# Power.net
KiCad netlist of a schematic drawn in Altium Designer
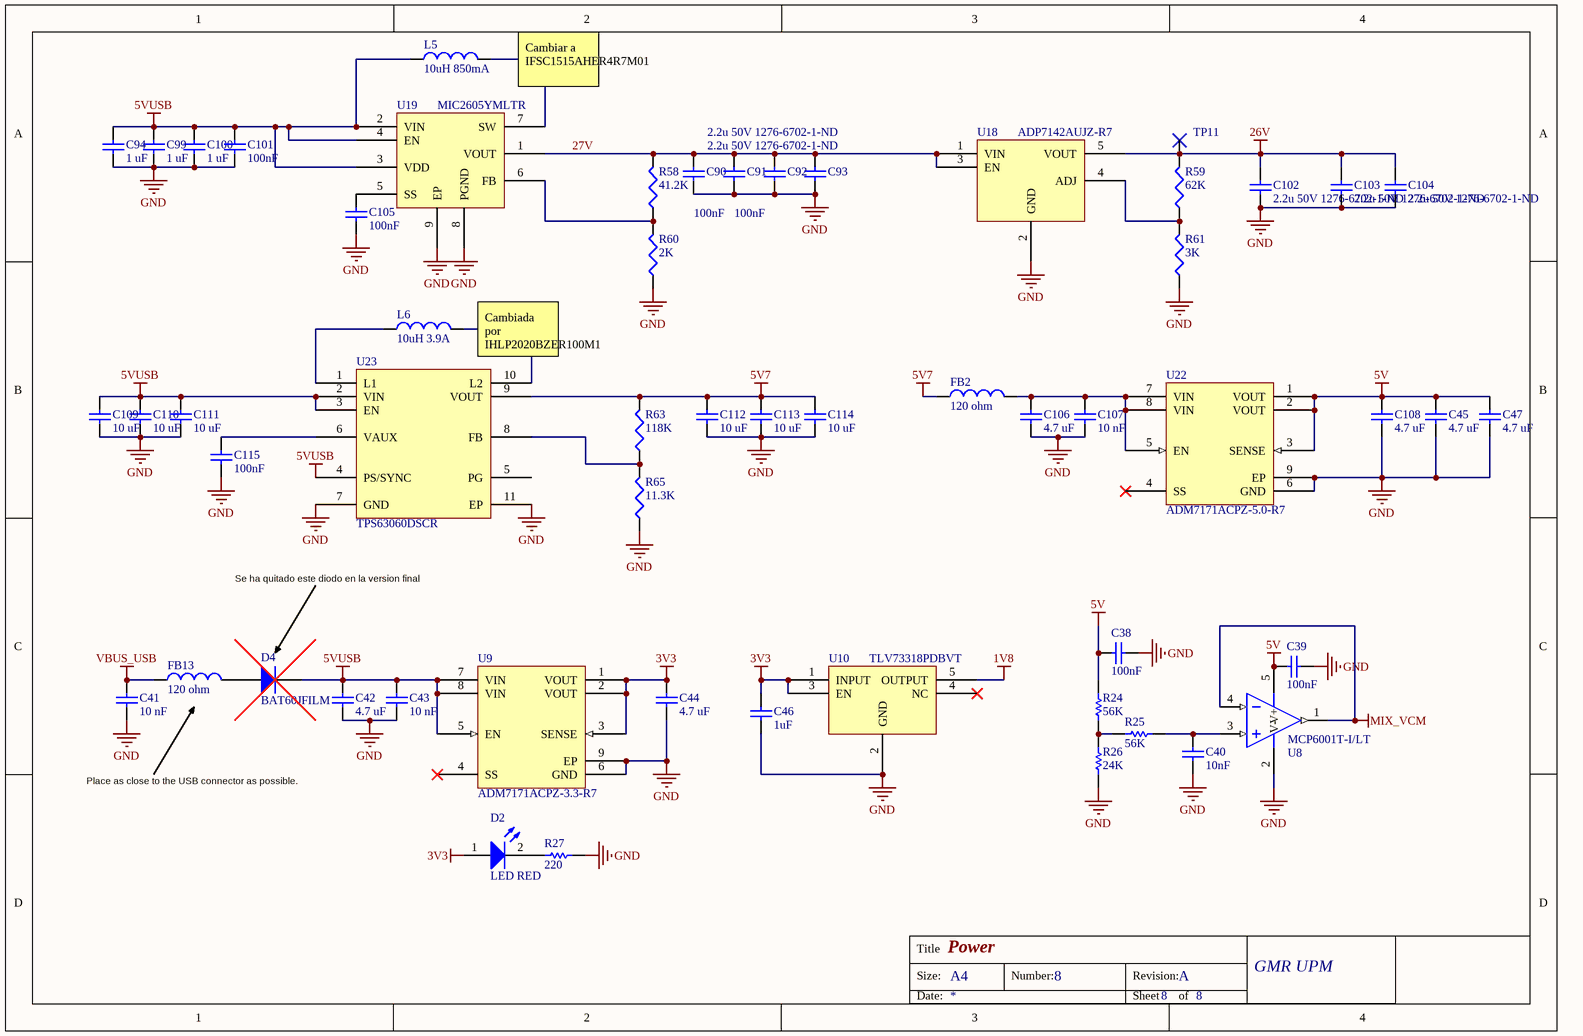
[diagram p0: Power.SchDoc]

(export (version "E")
  (design (tool "Eeschema 10.0.6"))
  (components
    (comp (ref "C38")
      (value "100nF")
      (footprint "0603 Cap")
      (description "CAP CER 16V X7R 0603")
      (fields (field (name "TOLERANCE") "10") (field (name "VOLTAGE") "16"))
      (libsource (lib "Componentes_base") (part "C_0603"))
    )
    (comp (ref "C39")
      (value "100nF")
      (footprint "0603 Cap")
      (description "CAP CER 16V X7R 0603")
      (fields (field (name "TOLERANCE") "10") (field (name "VOLTAGE") "16"))
      (libsource (lib "Componentes_base") (part "C_0603"))
    )
    (comp (ref "C40")
      (value "10nF")
      (footprint "0603 Cap")
      (description "CAP CER 16V X7R 0603")
      (fields (field (name "TOLERANCE") "10") (field (name "VOLTAGE") "16"))
      (libsource (lib "Componentes_base") (part "C_0603"))
    )
    (comp (ref "C41")
      (value "10 nF")
      (footprint "Chip2PinSM127P600-8N_CAP0402")
      (description "CAP CER 10000PF 25V X7R 0402")
      (fields
        (field (name "MANUFACTURER") "Samsung Electro-Mechanics America, Inc.")
        (field (name "MANUFACTURER PART NUMBER") "CL05B103KA5NNNC")
      )
      (libsource (lib "Components") (part "CL05B103KA5NNNC"))
    )
    (comp (ref "C42")
      (value "4.7 uF")
      (footprint "CAPC1608X10L")
      (description "Multilayer Ceramic Capacitors MLCC - SMD/SMT 0603 4.7uF 16volts X5R + - 10%")
      (fields
        (field (name "MANUFACTURER") "Murata Electronics")
        (field (name "MANUFACTURER PART NUMBER") "GRM188R61C475KAAJD")
      )
      (libsource (lib "Components") (part "GRM188R61C475KAAJD"))
    )
    (comp (ref "C43")
      (value "10 nF")
      (footprint "Chip2PinSM127P600-8N_CAP0402")
      (description "CAP CER 10000PF 25V X7R 0402")
      (fields
        (field (name "MANUFACTURER") "Samsung Electro-Mechanics America, Inc.")
        (field (name "MANUFACTURER PART NUMBER") "CL05B103KA5NNNC")
      )
      (libsource (lib "Components") (part "CL05B103KA5NNNC"))
    )
    (comp (ref "C44")
      (value "4.7 uF")
      (footprint "CAPC1608X10L")
      (description "Multilayer Ceramic Capacitors MLCC - SMD/SMT 0603 4.7uF 16volts X5R + - 10%")
      (fields
        (field (name "MANUFACTURER") "Murata Electronics")
        (field (name "MANUFACTURER PART NUMBER") "GRM188R61C475KAAJD")
      )
      (libsource (lib "Components") (part "GRM188R61C475KAAJD"))
    )
    (comp (ref "C45")
      (value "4.7 uF")
      (footprint "CAPC1608X10L")
      (description "Multilayer Ceramic Capacitors MLCC - SMD/SMT 0603 4.7uF 16volts X5R + - 10%")
      (fields
        (field (name "MANUFACTURER") "Murata Electronics")
        (field (name "MANUFACTURER PART NUMBER") "GRM188R61C475KAAJD")
      )
      (libsource (lib "Components") (part "GRM188R61C475KAAJD"))
    )
    (comp (ref "C46")
      (value "1uF")
      (footprint "0603 Cap")
      (description "CAP CER 1UF 16V X7R 0603")
      (fields
        (field (name "MANUFACTURER") "Samsung Electro-Mechanics America, Inc.")
        (field (name "MANUFACTURER PART NUMBER") "CL10B105MO8NNWC")
      )
      (libsource (lib "Componentes_base") (part "CL10B105MO8NNWC"))
    )
    (comp (ref "C47")
      (value "4.7 uF")
      (footprint "CAPC1608X10L")
      (description "Multilayer Ceramic Capacitors MLCC - SMD/SMT 0603 4.7uF 16volts X5R + - 10%")
      (fields
        (field (name "MANUFACTURER") "Murata Electronics")
        (field (name "MANUFACTURER PART NUMBER") "GRM188R61C475KAAJD")
      )
      (libsource (lib "Components") (part "GRM188R61C475KAAJD"))
    )
    (comp (ref "C90")
      (value "100nF")
      (footprint "0603 Cap")
      (description "CAP CER 0.1UF 16V X7R 0603")
      (fields
        (field (name "MANUFACTURER") "KEMET")
        (field (name "MANUFACTURER PART NUMBER") "C0603C104K4RACTU")
      )
      (libsource (lib "Componentes_base") (part "C0603C104K4RACTU"))
    )
    (comp (ref "C91")
      (value "100nF")
      (footprint "0603 Cap")
      (description "CAP CER 0.1UF 16V X7R 0603")
      (fields
        (field (name "MANUFACTURER") "KEMET")
        (field (name "MANUFACTURER PART NUMBER") "C0603C104K4RACTU")
      )
      (libsource (lib "Componentes_base") (part "C0603C104K4RACTU"))
    )
    (comp (ref "C92")
      (value "2.2u 50V 1276-6702-1-ND")
      (footprint "0805 CAP")
      (description "Multilayer Ceramic Capacitors MLCC - SMD/SMT 16volts 3.3uF X5R 10%")
      (fields
        (field (name "MANUFACTURER") "Kemet")
        (field (name "MANUFACTURER PART NUMBER") "C0805C335K4PACTU")
      )
      (libsource (lib "Componentes_base") (part "C0805C335K4PACTU"))
    )
    (comp (ref "C93")
      (value "2.2u 50V 1276-6702-1-ND")
      (footprint "0805 CAP")
      (description "Multilayer Ceramic Capacitors MLCC - SMD/SMT 16volts 3.3uF X5R 10%")
      (fields
        (field (name "MANUFACTURER") "Kemet")
        (field (name "MANUFACTURER PART NUMBER") "C0805C335K4PACTU")
      )
      (libsource (lib "Componentes_base") (part "C0805C335K4PACTU"))
    )
    (comp (ref "C94")
      (value "1 uF")
      (footprint "CAPC2012X08L")
      (description "CAP CER 1UF 25V 10% X7R 0805")
      (fields
        (field (name "MANUFACTURER") "Samsung Electro-Mechanics America, Inc")
        (field (name "MANUFACTURER PART NUMBER") "CL21B105KAFNNNE")
      )
      (libsource (lib "Componentes_base") (part "CL21B105KAFNNNE"))
    )
    (comp (ref "C99")
      (value "1 uF")
      (footprint "CAPC2012X08L")
      (description "CAP CER 1UF 25V 10% X7R 0805")
      (fields
        (field (name "MANUFACTURER") "Samsung Electro-Mechanics America, Inc")
        (field (name "MANUFACTURER PART NUMBER") "CL21B105KAFNNNE")
      )
      (libsource (lib "Componentes_base") (part "CL21B105KAFNNNE"))
    )
    (comp (ref "C100")
      (value "1 uF")
      (footprint "CAPC2012X08L")
      (description "CAP CER 1UF 25V 10% X7R 0805")
      (fields
        (field (name "MANUFACTURER") "Samsung Electro-Mechanics America, Inc")
        (field (name "MANUFACTURER PART NUMBER") "CL21B105KAFNNNE")
      )
      (libsource (lib "Componentes_base") (part "CL21B105KAFNNNE"))
    )
    (comp (ref "C101")
      (value "100nF")
      (footprint "0603 Cap")
      (description "CAP CER 0.1UF 16V X7R 0603")
      (fields
        (field (name "MANUFACTURER") "KEMET")
        (field (name "MANUFACTURER PART NUMBER") "C0603C104K4RACTU")
      )
      (libsource (lib "Componentes_base") (part "C0603C104K4RACTU"))
    )
    (comp (ref "C102")
      (value "2.2u 50V 1276-6702-1-ND")
      (footprint "0805 CAP")
      (description "Multilayer Ceramic Capacitors MLCC - SMD/SMT 16volts 3.3uF X5R 10%")
      (fields
        (field (name "MANUFACTURER") "Kemet")
        (field (name "MANUFACTURER PART NUMBER") "C0805C335K4PACTU")
      )
      (libsource (lib "Componentes_base") (part "C0805C335K4PACTU"))
    )
    (comp (ref "C103")
      (value "2.2u 50V 1276-6702-1-ND")
      (footprint "0805 CAP")
      (description "Multilayer Ceramic Capacitors MLCC - SMD/SMT 16volts 3.3uF X5R 10%")
      (fields
        (field (name "MANUFACTURER") "Kemet")
        (field (name "MANUFACTURER PART NUMBER") "C0805C335K4PACTU")
      )
      (libsource (lib "Componentes_base") (part "C0805C335K4PACTU"))
    )
    (comp (ref "C104")
      (value "2.2u 50V 1276-6702-1-ND")
      (footprint "0805 CAP")
      (description "Multilayer Ceramic Capacitors MLCC - SMD/SMT 16volts 3.3uF X5R 10%")
      (fields
        (field (name "MANUFACTURER") "Kemet")
        (field (name "MANUFACTURER PART NUMBER") "C0805C335K4PACTU")
      )
      (libsource (lib "Componentes_base") (part "C0805C335K4PACTU"))
    )
    (comp (ref "C105")
      (value "100nF")
      (footprint "0603 Cap")
      (description "CAP CER 0.1UF 16V X7R 0603")
      (fields
        (field (name "MANUFACTURER") "KEMET")
        (field (name "MANUFACTURER PART NUMBER") "C0603C104K4RACTU")
      )
      (libsource (lib "Componentes_base") (part "C0603C104K4RACTU"))
    )
    (comp (ref "C106")
      (value "4.7 uF")
      (footprint "CAPC1608X10L")
      (description "Multilayer Ceramic Capacitors MLCC - SMD/SMT 0603 4.7uF 16volts X5R + - 10%")
      (fields
        (field (name "MANUFACTURER") "Murata Electronics")
        (field (name "MANUFACTURER PART NUMBER") "GRM188R61C475KAAJD")
      )
      (libsource (lib "Components") (part "GRM188R61C475KAAJD"))
    )
    (comp (ref "C107")
      (value "10 nF")
      (footprint "Chip2PinSM127P600-8N_CAP0402")
      (description "CAP CER 10000PF 25V X7R 0402")
      (fields
        (field (name "MANUFACTURER") "Samsung Electro-Mechanics America, Inc.")
        (field (name "MANUFACTURER PART NUMBER") "CL05B103KA5NNNC")
      )
      (libsource (lib "Components") (part "CL05B103KA5NNNC"))
    )
    (comp (ref "C108")
      (value "4.7 uF")
      (footprint "CAPC1608X10L")
      (description "Multilayer Ceramic Capacitors MLCC - SMD/SMT 0603 4.7uF 16volts X5R + - 10%")
      (fields
        (field (name "MANUFACTURER") "Murata Electronics")
        (field (name "MANUFACTURER PART NUMBER") "GRM188R61C475KAAJD")
      )
      (libsource (lib "Components") (part "GRM188R61C475KAAJD"))
    )
    (comp (ref "C109")
      (value "10 uF")
      (footprint "CAPC2012X08L")
      (description "CAP CER 10UF 25V 10% X5R 0805")
      (fields
        (field (name "MANUFACTURER") "Samsung Electro-Mechanics America, Inc")
        (field (name "MANUFACTURER PART NUMBER") "CL21A106KAYNNNE")
      )
      (libsource (lib "Componentes_base") (part "CL21A106KAYNNNE"))
    )
    (comp (ref "C110")
      (value "10 uF")
      (footprint "CAPC2012X08L")
      (description "CAP CER 10UF 25V 10% X5R 0805")
      (fields
        (field (name "MANUFACTURER") "Samsung Electro-Mechanics America, Inc")
        (field (name "MANUFACTURER PART NUMBER") "CL21A106KAYNNNE")
      )
      (libsource (lib "Componentes_base") (part "CL21A106KAYNNNE"))
    )
    (comp (ref "C111")
      (value "10 uF")
      (footprint "CAPC2012X08L")
      (description "CAP CER 10UF 25V 10% X5R 0805")
      (fields
        (field (name "MANUFACTURER") "Samsung Electro-Mechanics America, Inc")
        (field (name "MANUFACTURER PART NUMBER") "CL21A106KAYNNNE")
      )
      (libsource (lib "Componentes_base") (part "CL21A106KAYNNNE"))
    )
    (comp (ref "C112")
      (value "10 uF")
      (footprint "CAPC2012X08L")
      (description "CAP CER 10UF 25V 10% X5R 0805")
      (fields
        (field (name "MANUFACTURER") "Samsung Electro-Mechanics America, Inc")
        (field (name "MANUFACTURER PART NUMBER") "CL21A106KAYNNNE")
      )
      (libsource (lib "Componentes_base") (part "CL21A106KAYNNNE"))
    )
    (comp (ref "C113")
      (value "10 uF")
      (footprint "CAPC2012X08L")
      (description "CAP CER 10UF 25V 10% X5R 0805")
      (fields
        (field (name "MANUFACTURER") "Samsung Electro-Mechanics America, Inc")
        (field (name "MANUFACTURER PART NUMBER") "CL21A106KAYNNNE")
      )
      (libsource (lib "Componentes_base") (part "CL21A106KAYNNNE"))
    )
    (comp (ref "C114")
      (value "10 uF")
      (footprint "CAPC2012X08L")
      (description "CAP CER 10UF 25V 10% X5R 0805")
      (fields
        (field (name "MANUFACTURER") "Samsung Electro-Mechanics America, Inc")
        (field (name "MANUFACTURER PART NUMBER") "CL21A106KAYNNNE")
      )
      (libsource (lib "Componentes_base") (part "CL21A106KAYNNNE"))
    )
    (comp (ref "C115")
      (value "100nF")
      (footprint "0603 Cap")
      (description "CAP CER 0.1UF 16V X7R 0603")
      (fields
        (field (name "MANUFACTURER") "KEMET")
        (field (name "MANUFACTURER PART NUMBER") "C0603C104K4RACTU")
      )
      (libsource (lib "Componentes_base") (part "C0603C104K4RACTU"))
    )
    (comp (ref "D2")
      (value "LED RED")
      (footprint "0603 LED")
      (description "LED RED CLEAR 0603 SMD")
      (fields
        (field (name "MANUFACTURER") "Lite-On Inc.")
        (field (name "MANUFACTURER PART NUMBER") "LTST-C191KRKT")
      )
      (libsource (lib "Componentes_base") (part "LTST-C191KRKT"))
    )
    (comp (ref "D4")
      (value "BAT60JFILM")
      (footprint "SODFL250X117-2N")
      (description "DIODE SCHOTTKY 10V 3A SOD323")
      (fields (field (name "MANUFACTURER") "STMicroelectronics"))
      (libsource (lib "Componentes_base") (part "BAT60JFILM"))
    )
    (comp (ref "FB2")
      (value "120 ohm")
      (footprint "INDC1608X08L")
      (description "FERRITE BEAD 120 OHM 0603 1LN")
      (fields
        (field (name "MANUFACTURER") "Murata Electronics North America")
        (field (name "MANUFACTURER PART NUMBER") "BLM18PG121SN1D")
      )
      (libsource (lib "Componentes_base") (part "BLM18PG121SN1D"))
    )
    (comp (ref "FB13")
      (value "120 ohm")
      (footprint "INDC1608X08L")
      (description "FERRITE BEAD 120 OHM 0603 1LN")
      (fields
        (field (name "MANUFACTURER") "Murata Electronics North America")
        (field (name "MANUFACTURER PART NUMBER") "BLM18PG121SN1D")
      )
      (libsource (lib "Componentes_base") (part "BLM18PG121SN1D"))
    )
    (comp (ref "L5")
      (value "10uH 850mA")
      (footprint "INDP4040X20N")
      (description "FIXED IND 10UH 850MA 185 MOHM")
      (fields
        (field (name "MANUFACTURER") "TDK")
        (field (name "MANUFACTURER PART NUMBER") "VLCF4020T-100MR85")
      )
      (libsource (lib "Schlib1") (part "VLCF4020T-100MR85"))
    )
    (comp (ref "L6")
      (value "10uH 3.9A")
      (footprint "INDP8080X45N")
      (description "Ind Power Shielded 10uH 20% 100KHz Ferrite 3.9A T/R")
      (fields
        (field (name "MANUFACTURER") "Murata")
        (field (name "MANUFACTURER PART NUMBER") "1217AS-H-100M=P3")
      )
      (libsource (lib "Schlib1") (part "1217AS-H-100M=P3"))
    )
    (comp (ref "R24")
      (value "56K")
      (footprint "0603 Res")
      (description "SMD Resistor, 1%, 0.1W, 0603")
      (fields (field (name "TOLERANCE") "1"))
      (libsource (lib "Componentes_base") (part "R_0603"))
    )
    (comp (ref "R25")
      (value "56K")
      (footprint "0603 Res")
      (description "SMD Resistor, 1%, 0.1W, 0603")
      (fields (field (name "TOLERANCE") "1"))
      (libsource (lib "Componentes_base") (part "R_0603"))
    )
    (comp (ref "R26")
      (value "24K")
      (footprint "0603 Res")
      (description "SMD Resistor, 1%, 0.1W, 0603")
      (fields (field (name "TOLERANCE") "1"))
      (libsource (lib "Componentes_base") (part "R_0603"))
    )
    (comp (ref "R27")
      (value "220")
      (footprint "0603 Res")
      (description "RES SMD 220 OHM 1% 1/10W 0603")
      (fields
        (field (name "MANUFACTURER") "Yageo")
        (field (name "MANUFACTURER PART NUMBER") "RC0603FR-07220RL")
      )
      (libsource (lib "Componentes_base") (part "RC0603FR-07220RL"))
    )
    (comp (ref "R58")
      (value "41.2K")
      (footprint "J1-0603")
      (description "Resistor")
      (fields (field (name "PUBLISHER") "Altium Limited"))
      (libsource (lib "Miscellaneous Devices") (part "Res3"))
    )
    (comp (ref "R59")
      (value "62K")
      (footprint "J1-0603")
      (description "Resistor")
      (fields (field (name "PUBLISHER") "Altium Limited"))
      (libsource (lib "Miscellaneous Devices") (part "Res3"))
    )
    (comp (ref "R60")
      (value "2K")
      (footprint "J1-0603")
      (description "Resistor")
      (fields (field (name "PUBLISHER") "Altium Limited"))
      (libsource (lib "Miscellaneous Devices") (part "Res3"))
    )
    (comp (ref "R61")
      (value "3K")
      (footprint "J1-0603")
      (description "Resistor")
      (fields (field (name "PUBLISHER") "Altium Limited"))
      (libsource (lib "Miscellaneous Devices") (part "Res3"))
    )
    (comp (ref "R63")
      (value "118K")
      (footprint "J1-0603")
      (description "Resistor")
      (fields (field (name "PUBLISHER") "Altium Limited"))
      (libsource (lib "Miscellaneous Devices") (part "Res3"))
    )
    (comp (ref "R65")
      (value "11.3K")
      (footprint "J1-0603")
      (description "Resistor")
      (fields (field (name "PUBLISHER") "Altium Limited"))
      (libsource (lib "Miscellaneous Devices") (part "Res3"))
    )
    (comp (ref "TP11")
      (value "TEST_POINT_PIN")
      (footprint "TESTPOINT 1mm")
      (description "Test point for single pin")
      (libsource (lib "Componentes_base") (part "TEST_POINT_PIN"))
    )
    (comp (ref "U8")
      (value "MCP6001T-I/LT")
      (footprint "SC70P210X110-5L")
      (description "Operational Amplifiers - Op Amps Single 1.8V 1MHz")
      (fields (field (name "MANUFACTURER") "Microchip Technology"))
      (libsource (lib "Componentes_base") (part "MCP6001T-I/LT"))
    )
    (comp (ref "U9")
      (value "ADM7171ACPZ-3.3-R7")
      (footprint "SON50P300X80_HS-9N LFCSP_WD Analog")
      (description "IC REG LDO 3.3V 1A 8-LFCSP")
      (fields (field (name "MANUFACTURER") "Analog Devices Inc."))
      (libsource (lib "Components") (part "ADM7171ACPZ-3.3-R7"))
    )
    (comp (ref "U10")
      (value "TLV73318PDBVT")
      (footprint "SOT95P280X110-5N")
      (fields (field (name "MANUFACTURER") "Texas Instruments"))
      (libsource (lib "Componentes_base") (part "TLV73318PDBVT"))
    )
    (comp (ref "U18")
      (value "ADP7142AUJZ-R7")
      (footprint "SOT95P280X90-5N")
      (description "LDO Voltage Regulators 40V 200mA LDO adjVo")
      (fields (field (name "MANUFACTURER") "Analog Devices"))
      (libsource (lib "Schlib1") (part "ADP7142AUJZ-R7"))
    )
    (comp (ref "U19")
      (value "MIC2605YMLTR")
      (footprint "SON50P200X90_HS-9N")
      (fields (field (name "MANUFACTURER") "Microchip Micrel"))
      (libsource (lib "Schlib1") (part "MIC2605YMLTR"))
    )
    (comp (ref "U22")
      (value "ADM7171ACPZ-5.0-R7")
      (footprint "SON50P300X80_HS-9N LFCSP_WD Analog")
      (description "LDO Regulator Pos 5V 1A 8-Pin LFCSP T/R")
      (fields (field (name "MANUFACTURER") "Analog Devices"))
      (libsource (lib "Schlib1") (part "ADM7171ACPZ-5.0-R7"))
    )
    (comp (ref "U23")
      (value "TPS63060DSCR")
      (footprint "SON50P300X80_HS-11N")
      (description "IC REG BUCK BOOST ADJ 2A 10WSON")
      (fields (field (name "MANUFACTURER") "Texas Instruments"))
      (libsource (lib "Schlib1") (part "TPS63060DSCR"))
    )
  )
  (nets
    (net (code "1") (name "/27V") (class "Default")
      (node (ref "C90") (pin "2") (pinfunction "2_2") (pintype "passive"))
      (node (ref "C91") (pin "2") (pinfunction "2_2") (pintype "passive"))
      (node (ref "C92") (pin "2") (pinfunction "2_2") (pintype "passive"))
      (node (ref "C93") (pin "2") (pinfunction "2_2") (pintype "passive"))
      (node (ref "R58") (pin "2") (pinfunction "2_2") (pintype "passive"))
      (node (ref "U18") (pin "1") (pinfunction "VIN_1") (pintype "passive"))
      (node (ref "U18") (pin "3") (pinfunction "EN_3") (pintype "passive"))
      (node (ref "U19") (pin "1") (pinfunction "VOUT_1") (pintype "passive"))
    )
    (net (code "2") (name "1V8") (class "Default")
      (node (ref "U10") (pin "5") (pinfunction "OUTPUT_5") (pintype "passive"))
    )
    (net (code "3") (name "3V3") (class "Default")
      (node (ref "C44") (pin "2") (pinfunction "2_2") (pintype "passive"))
      (node (ref "C46") (pin "2") (pinfunction "2_2") (pintype "passive"))
      (node (ref "D2") (pin "1") (pinfunction "A_1") (pintype "passive"))
      (node (ref "U10") (pin "1") (pinfunction "INPUT_1") (pintype "passive"))
      (node (ref "U10") (pin "3") (pinfunction "EN_3") (pintype "passive"))
      (node (ref "U9") (pin "1") (pinfunction "VOUT_1") (pintype "power_in"))
      (node (ref "U9") (pin "2") (pinfunction "VOUT_2") (pintype "power_in"))
      (node (ref "U9") (pin "3") (pinfunction "SENSE_3") (pintype "input"))
    )
    (net (code "4") (name "5V") (class "Default")
      (node (ref "C108") (pin "2") (pinfunction "2_2") (pintype "passive"))
      (node (ref "C38") (pin "1") (pinfunction "1_1") (pintype "passive"))
      (node (ref "C39") (pin "1") (pinfunction "1_1") (pintype "passive"))
      (node (ref "C45") (pin "2") (pinfunction "2_2") (pintype "passive"))
      (node (ref "C47") (pin "2") (pinfunction "2_2") (pintype "passive"))
      (node (ref "R24") (pin "2") (pinfunction "2_2") (pintype "passive"))
      (node (ref "U22") (pin "1") (pinfunction "VOUT_1") (pintype "power_in"))
      (node (ref "U22") (pin "2") (pinfunction "VOUT_2") (pintype "power_in"))
      (node (ref "U22") (pin "3") (pinfunction "SENSE_3") (pintype "input"))
      (node (ref "U8") (pin "5") (pinfunction "V+_5") (pintype "power_in"))
    )
    (net (code "5") (name "5V7") (class "Default")
      (node (ref "C112") (pin "2") (pinfunction "2_2") (pintype "passive"))
      (node (ref "C113") (pin "2") (pinfunction "2_2") (pintype "passive"))
      (node (ref "C114") (pin "2") (pinfunction "2_2") (pintype "passive"))
      (node (ref "FB2") (pin "1") (pinfunction "1_1") (pintype "passive"))
      (node (ref "R63") (pin "2") (pinfunction "2_2") (pintype "passive"))
      (node (ref "U23") (pin "9") (pinfunction "VOUT_9") (pintype "passive"))
    )
    (net (code "6") (name "5VUSB") (class "Default")
      (node (ref "C100") (pin "2") (pinfunction "2_2") (pintype "passive"))
      (node (ref "C101") (pin "2") (pinfunction "2_2") (pintype "passive"))
      (node (ref "C109") (pin "1") (pinfunction "1_1") (pintype "passive"))
      (node (ref "C110") (pin "2") (pinfunction "2_2") (pintype "passive"))
      (node (ref "C111") (pin "2") (pinfunction "2_2") (pintype "passive"))
      (node (ref "C42") (pin "2") (pinfunction "2_2") (pintype "passive"))
      (node (ref "C43") (pin "2") (pinfunction "2_2") (pintype "passive"))
      (node (ref "C94") (pin "2") (pinfunction "2_2") (pintype "passive"))
      (node (ref "C99") (pin "2") (pinfunction "2_2") (pintype "passive"))
      (node (ref "D4") (pin "1") (pinfunction "K_1") (pintype "passive"))
      (node (ref "L5") (pin "1") (pinfunction "1_1") (pintype "passive"))
      (node (ref "U19") (pin "2") (pinfunction "VIN_2") (pintype "passive"))
      (node (ref "U19") (pin "3") (pinfunction "VDD_3") (pintype "passive"))
      (node (ref "U19") (pin "4") (pinfunction "EN_4") (pintype "passive"))
      (node (ref "U23") (pin "2") (pinfunction "VIN_2") (pintype "passive"))
      (node (ref "U23") (pin "3") (pinfunction "EN_3") (pintype "passive"))
      (node (ref "U23") (pin "4") (pinfunction "PS/SYNC_4") (pintype "passive"))
      (node (ref "U9") (pin "5") (pinfunction "EN_5") (pintype "input"))
      (node (ref "U9") (pin "7") (pinfunction "VIN_7") (pintype "power_in"))
      (node (ref "U9") (pin "8") (pinfunction "VIN_8") (pintype "power_in"))
    )
    (net (code "7") (name "26V") (class "Default")
      (node (ref "C102") (pin "2") (pinfunction "2_2") (pintype "passive"))
      (node (ref "C103") (pin "2") (pinfunction "2_2") (pintype "passive"))
      (node (ref "C104") (pin "2") (pinfunction "2_2") (pintype "passive"))
      (node (ref "R59") (pin "2") (pinfunction "2_2") (pintype "passive"))
      (node (ref "TP11") (pin "1") (pinfunction "1_1") (pintype "passive"))
      (node (ref "U18") (pin "5") (pinfunction "VOUT_5") (pintype "passive"))
    )
    (net (code "8") (name "GND") (class "Default")
      (node (ref "C100") (pin "1") (pinfunction "1_1") (pintype "passive"))
      (node (ref "C101") (pin "1") (pinfunction "1_1") (pintype "passive"))
      (node (ref "C102") (pin "1") (pinfunction "1_1") (pintype "passive"))
      (node (ref "C103") (pin "1") (pinfunction "1_1") (pintype "passive"))
      (node (ref "C104") (pin "1") (pinfunction "1_1") (pintype "passive"))
      (node (ref "C105") (pin "1") (pinfunction "1_1") (pintype "passive"))
      (node (ref "C106") (pin "1") (pinfunction "1_1") (pintype "passive"))
      (node (ref "C107") (pin "1") (pinfunction "1_1") (pintype "passive"))
      (node (ref "C108") (pin "1") (pinfunction "1_1") (pintype "passive"))
      (node (ref "C109") (pin "2") (pinfunction "2_2") (pintype "passive"))
      (node (ref "C110") (pin "1") (pinfunction "1_1") (pintype "passive"))
      (node (ref "C111") (pin "1") (pinfunction "1_1") (pintype "passive"))
      (node (ref "C112") (pin "1") (pinfunction "1_1") (pintype "passive"))
      (node (ref "C113") (pin "1") (pinfunction "1_1") (pintype "passive"))
      (node (ref "C114") (pin "1") (pinfunction "1_1") (pintype "passive"))
      (node (ref "C115") (pin "1") (pinfunction "1_1") (pintype "passive"))
      (node (ref "C38") (pin "2") (pinfunction "2_2") (pintype "passive"))
      (node (ref "C39") (pin "2") (pinfunction "2_2") (pintype "passive"))
      (node (ref "C40") (pin "1") (pinfunction "1_1") (pintype "passive"))
      (node (ref "C41") (pin "1") (pinfunction "1_1") (pintype "passive"))
      (node (ref "C42") (pin "1") (pinfunction "1_1") (pintype "passive"))
      (node (ref "C43") (pin "1") (pinfunction "1_1") (pintype "passive"))
      (node (ref "C44") (pin "1") (pinfunction "1_1") (pintype "passive"))
      (node (ref "C45") (pin "1") (pinfunction "1_1") (pintype "passive"))
      (node (ref "C46") (pin "1") (pinfunction "1_1") (pintype "passive"))
      (node (ref "C47") (pin "1") (pinfunction "1_1") (pintype "passive"))
      (node (ref "C90") (pin "1") (pinfunction "1_1") (pintype "passive"))
      (node (ref "C91") (pin "1") (pinfunction "1_1") (pintype "passive"))
      (node (ref "C92") (pin "1") (pinfunction "1_1") (pintype "passive"))
      (node (ref "C93") (pin "1") (pinfunction "1_1") (pintype "passive"))
      (node (ref "C94") (pin "1") (pinfunction "1_1") (pintype "passive"))
      (node (ref "C99") (pin "1") (pinfunction "1_1") (pintype "passive"))
      (node (ref "R26") (pin "1") (pinfunction "1_1") (pintype "passive"))
      (node (ref "R27") (pin "2") (pinfunction "2_2") (pintype "passive"))
      (node (ref "R60") (pin "1") (pinfunction "1_1") (pintype "passive"))
      (node (ref "R61") (pin "1") (pinfunction "1_1") (pintype "passive"))
      (node (ref "R65") (pin "1") (pinfunction "1_1") (pintype "passive"))
      (node (ref "U10") (pin "2") (pinfunction "GND_2") (pintype "passive"))
      (node (ref "U18") (pin "2") (pinfunction "GND_2") (pintype "passive"))
      (node (ref "U19") (pin "8") (pinfunction "PGND_8") (pintype "passive"))
      (node (ref "U19") (pin "9") (pinfunction "EP_9") (pintype "passive"))
      (node (ref "U22") (pin "6") (pinfunction "GND_6") (pintype "power_in"))
      (node (ref "U22") (pin "9") (pinfunction "EP_9") (pintype "power_in"))
      (node (ref "U23") (pin "11") (pinfunction "EP_11") (pintype "passive"))
      (node (ref "U23") (pin "7") (pinfunction "GND_7") (pintype "passive"))
      (node (ref "U8") (pin "2") (pinfunction "V-_2") (pintype "power_in"))
      (node (ref "U9") (pin "6") (pinfunction "GND_6") (pintype "power_in"))
      (node (ref "U9") (pin "9") (pinfunction "EP_9") (pintype "power_in"))
    )
    (net (code "9") (name "MIX_VCM") (class "Default")
      (node (ref "U8") (pin "1") (pinfunction "OUT_1") (pintype "output"))
      (node (ref "U8") (pin "4") (pinfunction "IN-_4") (pintype "input"))
    )
    (net (code "10") (name "Net-(D2-C)") (class "Default")
      (node (ref "D2") (pin "2") (pinfunction "C_2") (pintype "passive"))
      (node (ref "R27") (pin "1") (pinfunction "1_1") (pintype "passive"))
    )
    (net (code "11") (name "Net-(D4-A)") (class "Default")
      (node (ref "D4") (pin "2") (pinfunction "A_2") (pintype "passive"))
      (node (ref "FB13") (pin "2") (pinfunction "2_2") (pintype "passive"))
    )
    (net (code "12") (name "Net-(R24-Pad1)") (class "Default")
      (node (ref "R24") (pin "1") (pinfunction "1_1") (pintype "passive"))
      (node (ref "R25") (pin "2") (pinfunction "2_2") (pintype "passive"))
      (node (ref "R26") (pin "2") (pinfunction "2_2") (pintype "passive"))
    )
    (net (code "13") (name "Net-(U8-IN+)") (class "Default")
      (node (ref "C40") (pin "2") (pinfunction "2_2") (pintype "passive"))
      (node (ref "R25") (pin "1") (pinfunction "1_1") (pintype "passive"))
      (node (ref "U8") (pin "3") (pinfunction "IN+_3") (pintype "input"))
    )
    (net (code "14") (name "Net-(U18-ADJ)") (class "Default")
      (node (ref "R59") (pin "1") (pinfunction "1_1") (pintype "passive"))
      (node (ref "R61") (pin "2") (pinfunction "2_2") (pintype "passive"))
      (node (ref "U18") (pin "4") (pinfunction "ADJ_4") (pintype "passive"))
    )
    (net (code "15") (name "Net-(U19-FB)") (class "Default")
      (node (ref "R58") (pin "1") (pinfunction "1_1") (pintype "passive"))
      (node (ref "R60") (pin "2") (pinfunction "2_2") (pintype "passive"))
      (node (ref "U19") (pin "6") (pinfunction "FB_6") (pintype "passive"))
    )
    (net (code "16") (name "Net-(U19-SS)") (class "Default")
      (node (ref "C105") (pin "2") (pinfunction "2_2") (pintype "passive"))
      (node (ref "U19") (pin "5") (pinfunction "SS_5") (pintype "passive"))
    )
    (net (code "17") (name "Net-(U19-SW)") (class "Default")
      (node (ref "L5") (pin "2") (pinfunction "2_2") (pintype "passive"))
      (node (ref "U19") (pin "7") (pinfunction "SW_7") (pintype "passive"))
    )
    (net (code "18") (name "Net-(U22-EN)") (class "Default")
      (node (ref "C106") (pin "2") (pinfunction "2_2") (pintype "passive"))
      (node (ref "C107") (pin "2") (pinfunction "2_2") (pintype "passive"))
      (node (ref "FB2") (pin "2") (pinfunction "2_2") (pintype "passive"))
      (node (ref "U22") (pin "5") (pinfunction "EN_5") (pintype "input"))
      (node (ref "U22") (pin "7") (pinfunction "VIN_7") (pintype "power_in"))
      (node (ref "U22") (pin "8") (pinfunction "VIN_8") (pintype "power_in"))
    )
    (net (code "19") (name "Net-(U23-FB)") (class "Default")
      (node (ref "R63") (pin "1") (pinfunction "1_1") (pintype "passive"))
      (node (ref "R65") (pin "2") (pinfunction "2_2") (pintype "passive"))
      (node (ref "U23") (pin "8") (pinfunction "FB_8") (pintype "passive"))
    )
    (net (code "20") (name "Net-(U23-L1)") (class "Default")
      (node (ref "L6") (pin "1") (pinfunction "1_1") (pintype "passive"))
      (node (ref "U23") (pin "1") (pinfunction "L1_1") (pintype "passive"))
    )
    (net (code "21") (name "Net-(U23-L2)") (class "Default")
      (node (ref "L6") (pin "2") (pinfunction "2_2") (pintype "passive"))
      (node (ref "U23") (pin "10") (pinfunction "L2_10") (pintype "passive"))
    )
    (net (code "22") (name "Net-(U23-VAUX)") (class "Default")
      (node (ref "C115") (pin "2") (pinfunction "2_2") (pintype "passive"))
      (node (ref "U23") (pin "6") (pinfunction "VAUX_6") (pintype "passive"))
    )
    (net (code "23") (name "VBUS_USB") (class "Default")
      (node (ref "C41") (pin "2") (pinfunction "2_2") (pintype "passive"))
      (node (ref "FB13") (pin "1") (pinfunction "1_1") (pintype "passive"))
    )
    (net (code "24") (name "unconnected-(U9-SS-Pad4)") (class "Default")
      (node (ref "U9") (pin "4") (pinfunction "SS_4") (pintype "passive+no_connect"))
    )
    (net (code "25") (name "unconnected-(U10-NC-Pad4)") (class "Default")
      (node (ref "U10") (pin "4") (pinfunction "NC_4") (pintype "passive+no_connect"))
    )
    (net (code "26") (name "unconnected-(U22-SS-Pad4)") (class "Default")
      (node (ref "U22") (pin "4") (pinfunction "SS_4") (pintype "passive+no_connect"))
    )
    (net (code "27") (name "unconnected-(U23-PG-Pad5)") (class "Default")
      (node (ref "U23") (pin "5") (pinfunction "PG_5") (pintype "passive"))
    )
  )
)
